# V2.net
KiCad netlist of a schematic drawn in Altium Designer
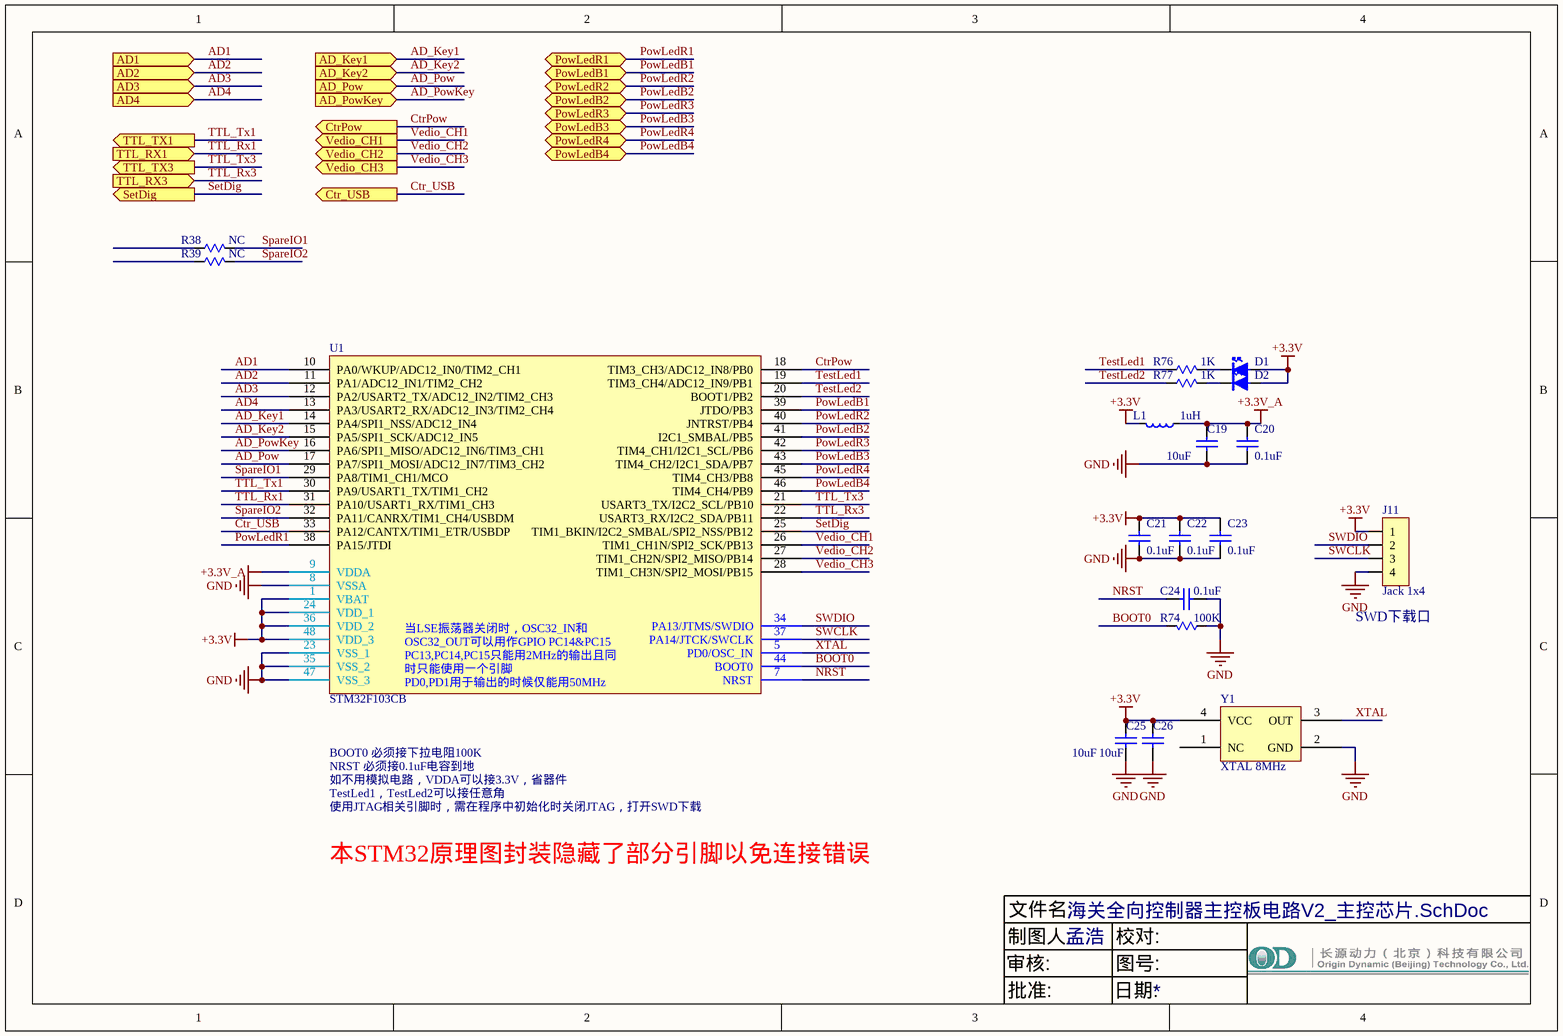
[diagram p0: 海关全向控制器主控板电路V2_主控芯片.SchDoc]

(export (version "E")
  (design (tool "Eeschema 10.0.6"))
  (components
    (comp (ref "C19")
      (value "10uF")
      (footprint "C0603")
      (description "Capacitor")
      (fields (field (name "PUBLISHER") "Altium Limited"))
      (libsource (lib "Miscellaneous Devices") (part "Cap"))
    )
    (comp (ref "C20")
      (value "0.1uF")
      (footprint "C0603")
      (description "Capacitor")
      (fields (field (name "PUBLISHER") "Altium Limited"))
      (libsource (lib "Miscellaneous Devices") (part "Cap"))
    )
    (comp (ref "C21")
      (value "0.1uF")
      (footprint "C0603")
      (description "Capacitor")
      (fields (field (name "PUBLISHER") "Altium Limited"))
      (libsource (lib "Miscellaneous Devices") (part "Cap"))
    )
    (comp (ref "C22")
      (value "0.1uF")
      (footprint "C0603")
      (description "Capacitor")
      (fields (field (name "PUBLISHER") "Altium Limited"))
      (libsource (lib "Miscellaneous Devices") (part "Cap"))
    )
    (comp (ref "C23")
      (value "0.1uF")
      (footprint "C0603")
      (description "Capacitor")
      (fields (field (name "PUBLISHER") "Altium Limited"))
      (libsource (lib "Miscellaneous Devices") (part "Cap"))
    )
    (comp (ref "C24")
      (value "0.1uF")
      (footprint "C0603")
      (description "Capacitor")
      (fields (field (name "PUBLISHER") "Altium Limited"))
      (libsource (lib "Miscellaneous Devices") (part "Cap"))
    )
    (comp (ref "C25")
      (value "10uF")
      (footprint "C0603")
      (description "Capacitor")
      (fields (field (name "PUBLISHER") "Altium Limited"))
      (libsource (lib "Miscellaneous Devices") (part "Cap"))
    )
    (comp (ref "C26")
      (value "10uF")
      (footprint "C0603")
      (description "Capacitor")
      (fields (field (name "PUBLISHER") "Altium Limited"))
      (libsource (lib "Miscellaneous Devices") (part "Cap"))
    )
    (comp (ref "D1")
      (value "LED")
      (footprint "LED0603")
      (libsource (lib "Passive Components Class") (part "LED"))
    )
    (comp (ref "D2")
      (value "LED")
      (footprint "LED0603")
      (libsource (lib "Passive Components Class") (part "LED"))
    )
    (comp (ref "J11")
      (value "Jack 1x4")
      (footprint "Jk1*4-2.0")
      (description "插座")
      (libsource (lib "Connector") (part "Jack 1x4"))
    )
    (comp (ref "L1")
      (value "1uH")
      (footprint "L0603")
      (description "INDUCTOR")
      (fields (field (name "PUBLISHER") "Altium Limited"))
      (libsource (lib "Passive Components Class") (part "INDUCTOR"))
    )
    (comp (ref "R38")
      (value "NC")
      (footprint "R0603")
      (description "Resistor")
      (fields (field (name "PUBLISHER") "Altium Limited"))
      (libsource (lib "UP-Robot") (part "Res"))
    )
    (comp (ref "R39")
      (value "NC")
      (footprint "R0603")
      (description "Resistor")
      (fields (field (name "PUBLISHER") "Altium Limited"))
      (libsource (lib "UP-Robot") (part "Res"))
    )
    (comp (ref "R74")
      (value "100K")
      (footprint "R0603")
      (description "Resistor")
      (fields (field (name "PUBLISHER") "Altium Limited"))
      (libsource (lib "Passive Components Class") (part "RES"))
    )
    (comp (ref "R76")
      (value "1K")
      (footprint "R0603")
      (description "Resistor")
      (fields (field (name "PUBLISHER") "Altium Limited"))
      (libsource (lib "UP-Robot") (part "Res"))
    )
    (comp (ref "R77")
      (value "1K")
      (footprint "R0603")
      (description "Resistor")
      (fields (field (name "PUBLISHER") "Altium Limited"))
      (libsource (lib "UP-Robot") (part "Res"))
    )
    (comp (ref "U1") (value "STM32F103CB") (footprint "LQF48") (libsource (lib "stm32") (part "STM32F103Cx")))
    (comp (ref "Y1") (value "XTAL 8MHz") (footprint "XTAL5032") (libsource (lib "Mic2805") (part "XTAL")))
  )
  (nets
    (net (code "1") (name "+3.3V") (class "Default")
      (node (ref "C21") (pin "1") (pinfunction "1_1") (pintype "passive"))
      (node (ref "C22") (pin "1") (pinfunction "1_1") (pintype "passive"))
      (node (ref "C23") (pin "1") (pinfunction "1_1") (pintype "passive"))
      (node (ref "C25") (pin "2") (pinfunction "2_2") (pintype "passive"))
      (node (ref "C26") (pin "2") (pinfunction "2_2") (pintype "passive"))
      (node (ref "D1") (pin "1") (pinfunction "A_1") (pintype "passive"))
      (node (ref "D2") (pin "1") (pinfunction "A_1") (pintype "passive"))
      (node (ref "J11") (pin "1") (pinfunction "1_1") (pintype "passive"))
      (node (ref "L1") (pin "1") (pinfunction "1_1") (pintype "passive"))
      (node (ref "U1") (pin "1") (pinfunction "VBAT_1") (pintype "power_in"))
      (node (ref "U1") (pin "24") (pinfunction "VDD_1_24") (pintype "power_in"))
      (node (ref "U1") (pin "36") (pinfunction "VDD_2_36") (pintype "power_in"))
      (node (ref "U1") (pin "48") (pinfunction "VDD_3_48") (pintype "power_in"))
      (node (ref "Y1") (pin "4") (pinfunction "VCC_4") (pintype "passive"))
    )
    (net (code "2") (name "+3.3V_A") (class "Default")
      (node (ref "C19") (pin "2") (pinfunction "2_2") (pintype "passive"))
      (node (ref "C20") (pin "1") (pinfunction "1_1") (pintype "passive"))
      (node (ref "L1") (pin "2") (pinfunction "2_2") (pintype "passive"))
      (node (ref "U1") (pin "9") (pinfunction "VDDA_9") (pintype "power_in"))
    )
    (net (code "3") (name "/AD1") (class "Default")
      (node (ref "U1") (pin "10") (pinfunction "PA0/WKUP/ADC12_IN0/TIM2_CH1_10") (pintype "passive"))
    )
    (net (code "4") (name "/AD2") (class "Default")
      (node (ref "U1") (pin "11") (pinfunction "PA1/ADC12_IN1/TIM2_CH2_11") (pintype "passive"))
    )
    (net (code "5") (name "/AD3") (class "Default")
      (node (ref "U1") (pin "12") (pinfunction "PA2/USART2_TX/ADC12_IN2/TIM2_CH3_12") (pintype "passive"))
    )
    (net (code "6") (name "/AD4") (class "Default")
      (node (ref "U1") (pin "13") (pinfunction "PA3/USART2_RX/ADC12_IN3/TIM2_CH4_13") (pintype "passive"))
    )
    (net (code "7") (name "/AD_Key1") (class "Default")
      (node (ref "U1") (pin "14") (pinfunction "PA4/SPI1_NSS/ADC12_IN4_14") (pintype "passive"))
    )
    (net (code "8") (name "/AD_Key2") (class "Default")
      (node (ref "U1") (pin "15") (pinfunction "PA5/SPI1_SCK/ADC12_IN5_15") (pintype "passive"))
    )
    (net (code "9") (name "/AD_Pow") (class "Default")
      (node (ref "U1") (pin "17") (pinfunction "PA7/SPI1_MOSI/ADC12_IN7/TIM3_CH2_17") (pintype "passive"))
    )
    (net (code "10") (name "/AD_PowKey") (class "Default")
      (node (ref "U1") (pin "16") (pinfunction "PA6/SPI1_MISO/ADC12_IN6/TIM3_CH1_16") (pintype "passive"))
    )
    (net (code "11") (name "/BOOT0") (class "Default")
      (node (ref "R74") (pin "2") (pinfunction "2_2") (pintype "passive"))
      (node (ref "U1") (pin "44") (pinfunction "BOOT0_44") (pintype "passive"))
    )
    (net (code "12") (name "/CtrPow") (class "Default")
      (node (ref "U1") (pin "18") (pinfunction "TIM3_CH3/ADC12_IN8/PB0_18") (pintype "passive"))
    )
    (net (code "13") (name "/Ctr_USB") (class "Default")
      (node (ref "U1") (pin "33") (pinfunction "PA12/CANTX/TIM1_ETR/USBDP_33") (pintype "passive"))
    )
    (net (code "14") (name "/NRST") (class "Default")
      (node (ref "C24") (pin "1") (pinfunction "1_1") (pintype "passive"))
      (node (ref "U1") (pin "7") (pinfunction "NRST_7") (pintype "passive"))
    )
    (net (code "15") (name "/PowLedB1") (class "Default")
      (node (ref "U1") (pin "39") (pinfunction "JTDO/PB3_39") (pintype "passive"))
    )
    (net (code "16") (name "/PowLedB2") (class "Default")
      (node (ref "U1") (pin "41") (pinfunction "I2C1_SMBAL/PB5_41") (pintype "passive"))
    )
    (net (code "17") (name "/PowLedB3") (class "Default")
      (node (ref "U1") (pin "43") (pinfunction "TIM4_CH2/I2C1_SDA/PB7_43") (pintype "passive"))
    )
    (net (code "18") (name "/PowLedB4") (class "Default")
      (node (ref "U1") (pin "46") (pinfunction "TIM4_CH4/PB9_46") (pintype "passive"))
    )
    (net (code "19") (name "/PowLedR1") (class "Default")
      (node (ref "U1") (pin "38") (pinfunction "PA15/JTDI_38") (pintype "passive"))
    )
    (net (code "20") (name "/PowLedR2") (class "Default")
      (node (ref "U1") (pin "40") (pinfunction "JNTRST/PB4_40") (pintype "passive"))
    )
    (net (code "21") (name "/PowLedR3") (class "Default")
      (node (ref "U1") (pin "42") (pinfunction "TIM4_CH1/I2C1_SCL/PB6_42") (pintype "passive"))
    )
    (net (code "22") (name "/PowLedR4") (class "Default")
      (node (ref "U1") (pin "45") (pinfunction "TIM4_CH3/PB8_45") (pintype "passive"))
    )
    (net (code "23") (name "/SWCLK") (class "Default")
      (node (ref "J11") (pin "3") (pinfunction "3_3") (pintype "passive"))
      (node (ref "U1") (pin "37") (pinfunction "PA14/JTCK/SWCLK_37") (pintype "passive"))
    )
    (net (code "24") (name "/SWDIO") (class "Default")
      (node (ref "J11") (pin "2") (pinfunction "2_2") (pintype "passive"))
      (node (ref "U1") (pin "34") (pinfunction "PA13/JTMS/SWDIO_34") (pintype "passive"))
    )
    (net (code "25") (name "/SetDig") (class "Default")
      (node (ref "U1") (pin "25") (pinfunction "TIM1_BKIN/I2C2_SMBAL/SPI2_NSS/PB12_25") (pintype "passive"))
    )
    (net (code "26") (name "/SpareIO1") (class "Default")
      (node (ref "R38") (pin "2") (pinfunction "2_2") (pintype "passive"))
      (node (ref "U1") (pin "29") (pinfunction "PA8/TIM1_CH1/MCO_29") (pintype "passive"))
    )
    (net (code "27") (name "/SpareIO2") (class "Default")
      (node (ref "R39") (pin "2") (pinfunction "2_2") (pintype "passive"))
      (node (ref "U1") (pin "32") (pinfunction "PA11/CANRX/TIM1_CH4/USBDM_32") (pintype "passive"))
    )
    (net (code "28") (name "/TTL_Rx1") (class "Default")
      (node (ref "U1") (pin "31") (pinfunction "PA10/USART1_RX/TIM1_CH3_31") (pintype "passive"))
    )
    (net (code "29") (name "/TTL_Rx3") (class "Default")
      (node (ref "U1") (pin "22") (pinfunction "USART3_RX/I2C2_SDA/PB11_22") (pintype "passive"))
    )
    (net (code "30") (name "/TTL_Tx1") (class "Default")
      (node (ref "U1") (pin "30") (pinfunction "PA9/USART1_TX/TIM1_CH2_30") (pintype "passive"))
    )
    (net (code "31") (name "/TTL_Tx3") (class "Default")
      (node (ref "U1") (pin "21") (pinfunction "USART3_TX/I2C2_SCL/PB10_21") (pintype "passive"))
    )
    (net (code "32") (name "/TestLed1") (class "Default")
      (node (ref "R76") (pin "1") (pinfunction "1_1") (pintype "passive"))
      (node (ref "U1") (pin "19") (pinfunction "TIM3_CH4/ADC12_IN9/PB1_19") (pintype "passive"))
    )
    (net (code "33") (name "/TestLed2") (class "Default")
      (node (ref "R77") (pin "1") (pinfunction "1_1") (pintype "passive"))
      (node (ref "U1") (pin "20") (pinfunction "BOOT1/PB2_20") (pintype "passive"))
    )
    (net (code "34") (name "/Vedio_CH1") (class "Default")
      (node (ref "U1") (pin "26") (pinfunction "TIM1_CH1N/SPI2_SCK/PB13_26") (pintype "passive"))
    )
    (net (code "35") (name "/Vedio_CH2") (class "Default")
      (node (ref "U1") (pin "27") (pinfunction "TIM1_CH2N/SPI2_MISO/PB14_27") (pintype "passive"))
    )
    (net (code "36") (name "/Vedio_CH3") (class "Default")
      (node (ref "U1") (pin "28") (pinfunction "TIM1_CH3N/SPI2_MOSI/PB15_28") (pintype "passive"))
    )
    (net (code "37") (name "/XTAL") (class "Default")
      (node (ref "U1") (pin "5") (pinfunction "PD0/OSC_IN_5") (pintype "passive"))
      (node (ref "Y1") (pin "3") (pinfunction "OUT_3") (pintype "passive"))
    )
    (net (code "38") (name "GND") (class "Default")
      (node (ref "C19") (pin "1") (pinfunction "1_1") (pintype "passive"))
      (node (ref "C20") (pin "2") (pinfunction "2_2") (pintype "passive"))
      (node (ref "C21") (pin "2") (pinfunction "2_2") (pintype "passive"))
      (node (ref "C22") (pin "2") (pinfunction "2_2") (pintype "passive"))
      (node (ref "C23") (pin "2") (pinfunction "2_2") (pintype "passive"))
      (node (ref "C24") (pin "2") (pinfunction "2_2") (pintype "passive"))
      (node (ref "C25") (pin "1") (pinfunction "1_1") (pintype "passive"))
      (node (ref "C26") (pin "1") (pinfunction "1_1") (pintype "passive"))
      (node (ref "J11") (pin "4") (pinfunction "4_4") (pintype "passive"))
      (node (ref "R74") (pin "1") (pinfunction "1_1") (pintype "passive"))
      (node (ref "U1") (pin "23") (pinfunction "VSS_1_23") (pintype "power_in"))
      (node (ref "U1") (pin "35") (pinfunction "VSS_2_35") (pintype "power_in"))
      (node (ref "U1") (pin "47") (pinfunction "VSS_3_47") (pintype "power_in"))
      (node (ref "U1") (pin "8") (pinfunction "VSSA_8") (pintype "power_in"))
      (node (ref "Y1") (pin "2") (pinfunction "GND_2") (pintype "passive"))
    )
    (net (code "39") (name "Net-(D1-K)") (class "Default")
      (node (ref "D1") (pin "2") (pinfunction "K_2") (pintype "passive"))
      (node (ref "R76") (pin "2") (pinfunction "2_2") (pintype "passive"))
    )
    (net (code "40") (name "Net-(D2-K)") (class "Default")
      (node (ref "D2") (pin "2") (pinfunction "K_2") (pintype "passive"))
      (node (ref "R77") (pin "2") (pinfunction "2_2") (pintype "passive"))
    )
    (net (code "41") (name "unconnected-(R38-Pad1)") (class "Default")
      (node (ref "R38") (pin "1") (pinfunction "1_1") (pintype "passive"))
    )
    (net (code "42") (name "unconnected-(R39-Pad1)") (class "Default")
      (node (ref "R39") (pin "1") (pinfunction "1_1") (pintype "passive"))
    )
    (net (code "43") (name "unconnected-(U1-PC13-TAMPER-RTC-Pad2)") (class "Default")
      (node (ref "U1") (pin "2") (pinfunction "PC13-TAMPER-RTC_2") (pintype "passive"))
    )
    (net (code "44") (name "unconnected-(U1-PC14-OSC32_IN-Pad3)") (class "Default")
      (node (ref "U1") (pin "3") (pinfunction "PC14-OSC32_IN_3") (pintype "passive"))
    )
    (net (code "45") (name "unconnected-(U1-PC15-OSC32_OUT-Pad4)") (class "Default")
      (node (ref "U1") (pin "4") (pinfunction "PC15-OSC32_OUT_4") (pintype "passive"))
    )
    (net (code "46") (name "unconnected-(U1-PD1{slash}OSC_OUT-Pad6)") (class "Default")
      (node (ref "U1") (pin "6") (pinfunction "PD1/OSC_OUT_6") (pintype "passive"))
    )
    (net (code "47") (name "unconnected-(Y1-NC-Pad1)") (class "Default")
      (node (ref "Y1") (pin "1") (pinfunction "NC_1") (pintype "passive"))
    )
  )
)
